# rs485.net
KiCad netlist of a schematic drawn in Altium Designer
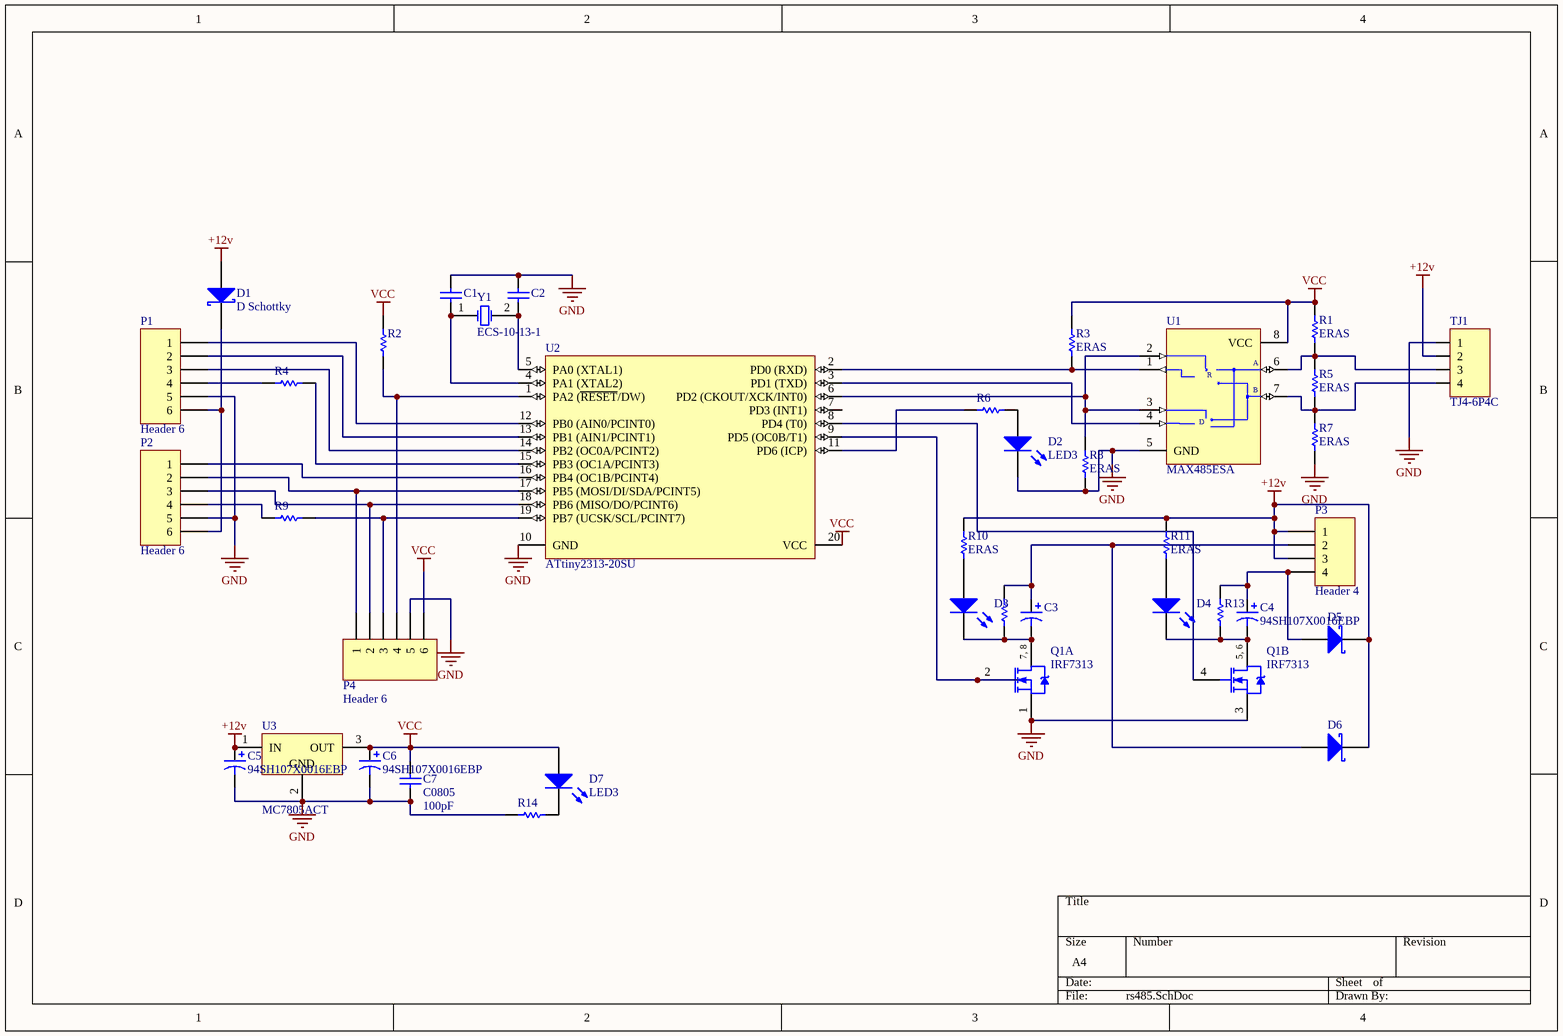
[diagram p0: rs485.SchDoc]

(export (version "E")
  (design (tool "Eeschema 10.0.6"))
  (components
    (comp (ref "C1")
      (value "C0805")
      (footprint "0805")
      (description "Ceramic Chip Capacitor - Standard")
      (fields (field (name "PUBLISHER") "Altium Limited"))
      (libsource (lib "KEMET Chip Capacitor") (part "C0805"))
    )
    (comp (ref "C2")
      (value "C0805")
      (footprint "0805")
      (description "Ceramic Chip Capacitor - Standard")
      (fields (field (name "PUBLISHER") "Altium Limited"))
      (libsource (lib "KEMET Chip Capacitor") (part "C0805"))
    )
    (comp (ref "C3")
      (value "94SH107X0016EBP")
      (footprint "E")
      (description "Solid Aluminum Capacitor with Organic Semiconductor Electrolyte: 100uF, 16V, Bulk Pack")
      (fields (field (name "PUBLISHER") "Altium Limited"))
      (libsource (lib "Vishay Electrolytic Radial-Lead Capacitor") (part "94SH107X0016EBP"))
    )
    (comp (ref "C4")
      (value "94SH107X0016EBP")
      (footprint "E")
      (description "Solid Aluminum Capacitor with Organic Semiconductor Electrolyte: 100uF, 16V, Bulk Pack")
      (fields (field (name "PUBLISHER") "Altium Limited"))
      (libsource (lib "Vishay Electrolytic Radial-Lead Capacitor") (part "94SH107X0016EBP"))
    )
    (comp (ref "C5")
      (value "94SH107X0016EBP")
      (footprint "E")
      (description "Solid Aluminum Capacitor with Organic Semiconductor Electrolyte: 100uF, 16V, Bulk Pack")
      (fields (field (name "PUBLISHER") "Altium Limited"))
      (libsource (lib "Vishay Electrolytic Radial-Lead Capacitor") (part "94SH107X0016EBP"))
    )
    (comp (ref "C6")
      (value "94SH107X0016EBP")
      (footprint "E")
      (description "Solid Aluminum Capacitor with Organic Semiconductor Electrolyte: 100uF, 16V, Bulk Pack")
      (fields (field (name "PUBLISHER") "Altium Limited"))
      (libsource (lib "Vishay Electrolytic Radial-Lead Capacitor") (part "94SH107X0016EBP"))
    )
    (comp (ref "C7")
      (value "C0805")
      (footprint "0805")
      (description "Ceramic Chip Capacitor - Standard")
      (fields (field (name "ALTIUM_VALUE") "100pF") (field (name "PUBLISHER") "Altium Limited"))
      (libsource (lib "KEMET Chip Capacitor") (part "C0805"))
    )
    (comp (ref "D1")
      (value "D Schottky")
      (footprint "SMB")
      (description "Schottky Diode")
      (fields (field (name "PUBLISHER") "Altium Limited"))
      (libsource (lib "Miscellaneous Devices") (part "D Schottky"))
    )
    (comp (ref "D2")
      (value "LED3")
      (footprint "3.5X2.8X1.9")
      (description "Typical BLUE SiC LED")
      (fields (field (name "PUBLISHER") "Altium Limited"))
      (libsource (lib "Miscellaneous Devices") (part "LED3"))
    )
    (comp (ref "D3")
      (value "LED3")
      (footprint "3.5X2.8X1.9")
      (description "Typical BLUE SiC LED")
      (fields (field (name "PUBLISHER") "Altium Limited"))
      (libsource (lib "Miscellaneous Devices") (part "LED3"))
    )
    (comp (ref "D4")
      (value "LED3")
      (footprint "3.5X2.8X1.9")
      (description "Typical BLUE SiC LED")
      (fields (field (name "PUBLISHER") "Altium Limited"))
      (libsource (lib "Miscellaneous Devices") (part "LED3"))
    )
    (comp (ref "D5")
      (value "D Schottky")
      (footprint "SMB")
      (description "Schottky Diode")
      (fields (field (name "PUBLISHER") "Altium Limited"))
      (libsource (lib "Miscellaneous Devices") (part "D Schottky"))
    )
    (comp (ref "D6")
      (value "D Schottky")
      (footprint "SMB")
      (description "Schottky Diode")
      (fields (field (name "PUBLISHER") "Altium Limited"))
      (libsource (lib "Miscellaneous Devices") (part "D Schottky"))
    )
    (comp (ref "D7")
      (value "LED3")
      (footprint "3.5X2.8X1.9")
      (description "Typical BLUE SiC LED")
      (fields (field (name "PUBLISHER") "Altium Limited"))
      (libsource (lib "Miscellaneous Devices") (part "LED3"))
    )
    (comp (ref "P1")
      (value "Header 6")
      (footprint "HDR1X6")
      (description "Header, 6-Pin")
      (fields (field (name "PUBLISHER") "Altium Limited"))
      (libsource (lib "") (part "Header 6_1"))
    )
    (comp (ref "P2")
      (value "Header 6")
      (footprint "HDR1X6")
      (description "Header, 6-Pin")
      (fields (field (name "PUBLISHER") "Altium Limited"))
      (libsource (lib "") (part "Header 6_1"))
    )
    (comp (ref "P3")
      (value "Header 4")
      (footprint "HDR1X4")
      (description "Header, 4-Pin")
      (fields (field (name "PUBLISHER") "Altium Limited"))
      (libsource (lib "Miscellaneous Connectors") (part "Header 4"))
    )
    (comp (ref "P4")
      (value "Header 6")
      (footprint "HDR1X6")
      (description "Header, 6-Pin")
      (fields (field (name "PUBLISHER") "Altium Limited"))
      (libsource (lib "Miscellaneous Connectors") (part "Header 6"))
    )
    (comp (ref "Q1")
      (value "IRF7313")
      (footprint "SO-8_N")
      (description "HEXFET Power MOSFET")
      (fields (field (name "PUBLISHER") "Altium Limited"))
      (libsource (lib "IR Discrete MOSFET - Power") (part "IRF7313"))
    )
    (comp (ref "R1")
      (value "ERAS")
      (footprint "ERA-0805")
      (fields (field (name "PUBLISHER") "Altium Limited"))
      (libsource (lib "Panasonic Resistor") (part "ERAS"))
    )
    (comp (ref "R2")
      (value "ERAS")
      (footprint "ERA-0805")
      (fields (field (name "PUBLISHER") "Altium Limited"))
      (libsource (lib "Panasonic Resistor") (part "ERAS"))
    )
    (comp (ref "R3")
      (value "ERAS")
      (footprint "ERA-0805")
      (fields (field (name "PUBLISHER") "Altium Limited"))
      (libsource (lib "Panasonic Resistor") (part "ERAS"))
    )
    (comp (ref "R4")
      (value "ERAS")
      (footprint "ERA-0805")
      (fields (field (name "PUBLISHER") "Altium Limited"))
      (libsource (lib "Panasonic Resistor") (part "ERAS"))
    )
    (comp (ref "R5")
      (value "ERAS")
      (footprint "ERA-0805")
      (fields (field (name "PUBLISHER") "Altium Limited"))
      (libsource (lib "Panasonic Resistor") (part "ERAS"))
    )
    (comp (ref "R6")
      (value "ERAS")
      (footprint "ERA-0805")
      (fields (field (name "PUBLISHER") "Altium Limited"))
      (libsource (lib "Panasonic Resistor") (part "ERAS"))
    )
    (comp (ref "R7")
      (value "ERAS")
      (footprint "ERA-0805")
      (fields (field (name "PUBLISHER") "Altium Limited"))
      (libsource (lib "Panasonic Resistor") (part "ERAS"))
    )
    (comp (ref "R8")
      (value "ERAS")
      (footprint "ERA-0805")
      (fields (field (name "PUBLISHER") "Altium Limited"))
      (libsource (lib "Panasonic Resistor") (part "ERAS"))
    )
    (comp (ref "R9")
      (value "ERAS")
      (footprint "ERA-0805")
      (fields (field (name "PUBLISHER") "Altium Limited"))
      (libsource (lib "Panasonic Resistor") (part "ERAS"))
    )
    (comp (ref "R10")
      (value "ERAS")
      (footprint "ERA-0805")
      (fields (field (name "PUBLISHER") "Altium Limited"))
      (libsource (lib "Panasonic Resistor") (part "ERAS"))
    )
    (comp (ref "R11")
      (value "ERAS")
      (footprint "ERA-0805")
      (fields (field (name "PUBLISHER") "Altium Limited"))
      (libsource (lib "Panasonic Resistor") (part "ERAS"))
    )
    (comp (ref "R12")
      (value "ERAS")
      (footprint "ERA-0805")
      (fields (field (name "PUBLISHER") "Altium Limited"))
      (libsource (lib "Panasonic Resistor") (part "ERAS"))
    )
    (comp (ref "R13")
      (value "ERAS")
      (footprint "ERA-0805")
      (fields (field (name "PUBLISHER") "Altium Limited"))
      (libsource (lib "Panasonic Resistor") (part "ERAS"))
    )
    (comp (ref "R14")
      (value "ERAS")
      (footprint "ERA-0805")
      (fields (field (name "PUBLISHER") "Altium Limited"))
      (libsource (lib "Panasonic Resistor") (part "ERAS"))
    )
    (comp (ref "TJ1") (value "TJ4-6P4C") (footprint "TJ4-6P4C") (libsource (lib "FAS") (part "TJ4-6P4C")))
    (comp (ref "U1")
      (value "MAX485ESA")
      (footprint "NSO8_N")
      (description "Low-Power, Slew-Rate-Limited RS-485/RS-422 Transceiver")
      (fields (field (name "PUBLISHER") "Altium Limited"))
      (libsource (lib "Maxim Communication Transceiver") (part "MAX485ESA"))
    )
    (comp (ref "U2")
      (value "ATtiny2313-20SU")
      (footprint "20S_N")
      (fields (field (name "PUBLISHER") "Altium Limited"))
      (libsource (lib "Atmel Microcontroller 8-Bit tinyAVR") (part "ATtiny2313-20SU"))
    )
    (comp (ref "U3")
      (value "MC7805ACT")
      (footprint "221A-06")
      (description "Three-Terminal Positive Voltage Regulator")
      (fields (field (name "PUBLISHER") "Altium Limited"))
      (libsource (lib "ON Semi Power Mgt Voltage Regulator") (part "MC7805ACT"))
    )
    (comp (ref "Y1")
      (value "ECS-10-13-1")
      (footprint "HC-49U")
      (description "Crystal Oscillator")
      (fields (field (name "PUBLISHER") "Altium Limited"))
      (libsource (lib "ECS Crystal Oscillator") (part "ECS-10-13-1"))
    )
  )
  (nets
    (net (code "1") (name "+12v") (class "Default")
      (node (ref "C5") (pin "1") (pinfunction "1_1") (pintype "passive"))
      (node (ref "D1") (pin "1") (pinfunction "A_1") (pintype "passive"))
      (node (ref "D5") (pin "2") (pinfunction "K_2") (pintype "passive"))
      (node (ref "D6") (pin "2") (pinfunction "K_2") (pintype "passive"))
      (node (ref "P3") (pin "1") (pinfunction "1_1") (pintype "passive"))
      (node (ref "P3") (pin "3") (pinfunction "3_3") (pintype "passive"))
      (node (ref "R10") (pin "1") (pinfunction "1_1") (pintype "passive"))
      (node (ref "R11") (pin "1") (pinfunction "1_1") (pintype "passive"))
      (node (ref "TJ1") (pin "2") (pinfunction "2_2") (pintype "passive"))
      (node (ref "U3") (pin "1") (pinfunction "IN_1") (pintype "power_in"))
    )
    (net (code "2") (name "GND") (class "Default")
      (node (ref "C1") (pin "1") (pinfunction "1_1") (pintype "passive"))
      (node (ref "C2") (pin "1") (pinfunction "1_1") (pintype "passive"))
      (node (ref "C5") (pin "2") (pinfunction "2_2") (pintype "passive"))
      (node (ref "C6") (pin "2") (pinfunction "2_2") (pintype "passive"))
      (node (ref "C7") (pin "1") (pinfunction "1_1") (pintype "passive"))
      (node (ref "D2") (pin "2") (pinfunction "K_2") (pintype "passive"))
      (node (ref "P1") (pin "5") (pinfunction "5_5") (pintype "passive"))
      (node (ref "P2") (pin "5") (pinfunction "5_5") (pintype "passive"))
      (node (ref "P4") (pin "5") (pinfunction "5_5") (pintype "passive"))
      (node (ref "Q1") (pin "1") (pinfunction "S_1") (pintype "passive"))
      (node (ref "Q1") (pin "3") (pinfunction "S_3") (pintype "passive"))
      (node (ref "R14") (pin "2") (pinfunction "2_2") (pintype "passive"))
      (node (ref "R7") (pin "2") (pinfunction "2_2") (pintype "passive"))
      (node (ref "R8") (pin "2") (pinfunction "2_2") (pintype "passive"))
      (node (ref "TJ1") (pin "1") (pinfunction "1_1") (pintype "passive"))
      (node (ref "U1") (pin "5") (pinfunction "GND_5") (pintype "power_in"))
      (node (ref "U2") (pin "10") (pinfunction "GND_10") (pintype "power_in"))
      (node (ref "U3") (pin "2") (pinfunction "GND_2") (pintype "power_in"))
    )
    (net (code "3") (name "Net-(D1-K)") (class "Default")
      (node (ref "D1") (pin "2") (pinfunction "K_2") (pintype "passive"))
      (node (ref "P1") (pin "6") (pinfunction "6_6") (pintype "passive"))
      (node (ref "P2") (pin "6") (pinfunction "6_6") (pintype "passive"))
    )
    (net (code "4") (name "Net-(D2-A)") (class "Default")
      (node (ref "D2") (pin "1") (pinfunction "A_1") (pintype "passive"))
      (node (ref "R6") (pin "2") (pinfunction "2_2") (pintype "passive"))
    )
    (net (code "5") (name "Net-(D3-A)") (class "Default")
      (node (ref "D3") (pin "1") (pinfunction "A_1") (pintype "passive"))
      (node (ref "R10") (pin "2") (pinfunction "2_2") (pintype "passive"))
    )
    (net (code "6") (name "Net-(D3-K)") (class "Default")
      (node (ref "C3") (pin "2") (pinfunction "2_2") (pintype "passive"))
      (node (ref "D3") (pin "2") (pinfunction "K_2") (pintype "passive"))
      (node (ref "Q1") (pin "7") (pinfunction "D_7") (pintype "passive"))
      (node (ref "Q1") (pin "8") (pinfunction "D_8") (pintype "passive"))
      (node (ref "R12") (pin "2") (pinfunction "2_2") (pintype "passive"))
    )
    (net (code "7") (name "Net-(D4-A)") (class "Default")
      (node (ref "D4") (pin "1") (pinfunction "A_1") (pintype "passive"))
      (node (ref "R11") (pin "2") (pinfunction "2_2") (pintype "passive"))
    )
    (net (code "8") (name "Net-(D4-K)") (class "Default")
      (node (ref "C4") (pin "2") (pinfunction "2_2") (pintype "passive"))
      (node (ref "D4") (pin "2") (pinfunction "K_2") (pintype "passive"))
      (node (ref "Q1") (pin "5") (pinfunction "D_5") (pintype "passive"))
      (node (ref "Q1") (pin "6") (pinfunction "D_6") (pintype "passive"))
      (node (ref "R13") (pin "2") (pinfunction "2_2") (pintype "passive"))
    )
    (net (code "9") (name "Net-(D5-A)") (class "Default")
      (node (ref "C4") (pin "1") (pinfunction "1_1") (pintype "passive"))
      (node (ref "D5") (pin "1") (pinfunction "A_1") (pintype "passive"))
      (node (ref "P3") (pin "4") (pinfunction "4_4") (pintype "passive"))
      (node (ref "R13") (pin "1") (pinfunction "1_1") (pintype "passive"))
    )
    (net (code "10") (name "Net-(D6-A)") (class "Default")
      (node (ref "C3") (pin "1") (pinfunction "1_1") (pintype "passive"))
      (node (ref "D6") (pin "1") (pinfunction "A_1") (pintype "passive"))
      (node (ref "P3") (pin "2") (pinfunction "2_2") (pintype "passive"))
      (node (ref "R12") (pin "1") (pinfunction "1_1") (pintype "passive"))
    )
    (net (code "11") (name "Net-(D7-K)") (class "Default")
      (node (ref "D7") (pin "2") (pinfunction "K_2") (pintype "passive"))
      (node (ref "R14") (pin "1") (pinfunction "1_1") (pintype "passive"))
    )
    (net (code "12") (name "Net-(P1-Pad4)") (class "Default")
      (node (ref "P1") (pin "4") (pinfunction "4_4") (pintype "passive"))
      (node (ref "R4") (pin "2") (pinfunction "2_2") (pintype "passive"))
    )
    (net (code "13") (name "Net-(P2-Pad4)") (class "Default")
      (node (ref "P2") (pin "4") (pinfunction "4_4") (pintype "passive"))
      (node (ref "R9") (pin "2") (pinfunction "2_2") (pintype "passive"))
    )
    (net (code "14") (name "Net-(Q1A-G)") (class "Default")
      (node (ref "Q1") (pin "2") (pinfunction "G_2") (pintype "passive"))
      (node (ref "U2") (pin "9") (pinfunction "PD5_(OC0B/T1)_9") (pintype "bidirectional"))
    )
    (net (code "15") (name "Net-(Q1B-G)") (class "Default")
      (node (ref "Q1") (pin "4") (pinfunction "G_4") (pintype "passive"))
      (node (ref "U2") (pin "8") (pinfunction "PD4_(T0)_8") (pintype "bidirectional"))
    )
    (net (code "16") (name "Net-(U1-A)") (class "Default")
      (node (ref "R1") (pin "2") (pinfunction "2_2") (pintype "passive"))
      (node (ref "R5") (pin "1") (pinfunction "1_1") (pintype "passive"))
      (node (ref "TJ1") (pin "3") (pinfunction "3_3") (pintype "passive"))
      (node (ref "U1") (pin "6") (pinfunction "A_6") (pintype "bidirectional"))
    )
    (net (code "17") (name "Net-(U1-B)") (class "Default")
      (node (ref "R5") (pin "2") (pinfunction "2_2") (pintype "passive"))
      (node (ref "R7") (pin "1") (pinfunction "1_1") (pintype "passive"))
      (node (ref "TJ1") (pin "4") (pinfunction "4_4") (pintype "passive"))
      (node (ref "U1") (pin "7") (pinfunction "B_7") (pintype "bidirectional"))
    )
    (net (code "18") (name "Net-(U1-DE)") (class "Default")
      (node (ref "R8") (pin "1") (pinfunction "1_1") (pintype "passive"))
      (node (ref "U1") (pin "2") (pinfunction "~{RE}_2") (pintype "input"))
      (node (ref "U1") (pin "3") (pinfunction "DE_3") (pintype "input"))
      (node (ref "U2") (pin "6") (pinfunction "PD2_(CKOUT/XCK/INT0)_6") (pintype "bidirectional"))
    )
    (net (code "19") (name "Net-(U1-DI)") (class "Default")
      (node (ref "U1") (pin "4") (pinfunction "DI_4") (pintype "input"))
      (node (ref "U2") (pin "3") (pinfunction "PD1_(TXD)_3") (pintype "bidirectional"))
    )
    (net (code "20") (name "Net-(U1-RO)") (class "Default")
      (node (ref "R3") (pin "2") (pinfunction "2_2") (pintype "passive"))
      (node (ref "U1") (pin "1") (pinfunction "RO_1") (pintype "output"))
      (node (ref "U2") (pin "2") (pinfunction "PD0_(RXD)_2") (pintype "bidirectional"))
    )
    (net (code "21") (name "Net-(U2-PA0_(XTAL1))") (class "Default")
      (node (ref "C2") (pin "2") (pinfunction "2_2") (pintype "passive"))
      (node (ref "U2") (pin "5") (pinfunction "PA0_(XTAL1)_5") (pintype "bidirectional"))
      (node (ref "Y1") (pin "2") (pinfunction "OSC2_2") (pintype "passive"))
    )
    (net (code "22") (name "Net-(U2-PA1_(XTAL2))") (class "Default")
      (node (ref "C1") (pin "2") (pinfunction "2_2") (pintype "passive"))
      (node (ref "U2") (pin "4") (pinfunction "PA1_(XTAL2)_4") (pintype "bidirectional"))
      (node (ref "Y1") (pin "1") (pinfunction "OSC1_1") (pintype "passive"))
    )
    (net (code "23") (name "Net-(U2-PA2_(~{RESET}{slash}DW))") (class "Default")
      (node (ref "P4") (pin "4") (pinfunction "4_4") (pintype "passive"))
      (node (ref "R2") (pin "2") (pinfunction "2_2") (pintype "passive"))
      (node (ref "U2") (pin "1") (pinfunction "PA2_(~{RESET}/DW)_1") (pintype "bidirectional"))
    )
    (net (code "24") (name "Net-(U2-PB0_(AIN0{slash}PCINT0))") (class "Default")
      (node (ref "P1") (pin "1") (pinfunction "1_1") (pintype "passive"))
      (node (ref "U2") (pin "12") (pinfunction "PB0_(AIN0/PCINT0)_12") (pintype "bidirectional"))
    )
    (net (code "25") (name "Net-(U2-PB1_(AIN1{slash}PCINT1))") (class "Default")
      (node (ref "P1") (pin "2") (pinfunction "2_2") (pintype "passive"))
      (node (ref "U2") (pin "13") (pinfunction "PB1_(AIN1/PCINT1)_13") (pintype "bidirectional"))
    )
    (net (code "26") (name "Net-(U2-PB2_(OC0A{slash}PCINT2))") (class "Default")
      (node (ref "P1") (pin "3") (pinfunction "3_3") (pintype "passive"))
      (node (ref "U2") (pin "14") (pinfunction "PB2_(OC0A/PCINT2)_14") (pintype "bidirectional"))
    )
    (net (code "27") (name "Net-(U2-PB3_(OC1A{slash}PCINT3))") (class "Default")
      (node (ref "R4") (pin "1") (pinfunction "1_1") (pintype "passive"))
      (node (ref "U2") (pin "15") (pinfunction "PB3_(OC1A/PCINT3)_15") (pintype "bidirectional"))
    )
    (net (code "28") (name "Net-(U2-PB4_(OC1B{slash}PCINT4))") (class "Default")
      (node (ref "P2") (pin "1") (pinfunction "1_1") (pintype "passive"))
      (node (ref "U2") (pin "16") (pinfunction "PB4_(OC1B/PCINT4)_16") (pintype "bidirectional"))
    )
    (net (code "29") (name "Net-(U2-PB5_(MOSI{slash}DI{slash}SDA{slash}PCINT5))") (class "Default")
      (node (ref "P2") (pin "2") (pinfunction "2_2") (pintype "passive"))
      (node (ref "P4") (pin "1") (pinfunction "1_1") (pintype "passive"))
      (node (ref "U2") (pin "17") (pinfunction "PB5_(MOSI/DI/SDA/PCINT5)_17") (pintype "bidirectional"))
    )
    (net (code "30") (name "Net-(U2-PB6_(MISO{slash}DO{slash}PCINT6))") (class "Default")
      (node (ref "P2") (pin "3") (pinfunction "3_3") (pintype "passive"))
      (node (ref "P4") (pin "2") (pinfunction "2_2") (pintype "passive"))
      (node (ref "U2") (pin "18") (pinfunction "PB6_(MISO/DO/PCINT6)_18") (pintype "bidirectional"))
    )
    (net (code "31") (name "Net-(U2-PB7_(UCSK{slash}SCL{slash}PCINT7))") (class "Default")
      (node (ref "P4") (pin "3") (pinfunction "3_3") (pintype "passive"))
      (node (ref "R9") (pin "1") (pinfunction "1_1") (pintype "passive"))
      (node (ref "U2") (pin "19") (pinfunction "PB7_(UCSK/SCL/PCINT7)_19") (pintype "bidirectional"))
    )
    (net (code "32") (name "Net-(U2-PD6_(ICP))") (class "Default")
      (node (ref "R6") (pin "1") (pinfunction "1_1") (pintype "passive"))
      (node (ref "U2") (pin "11") (pinfunction "PD6_(ICP)_11") (pintype "bidirectional"))
    )
    (net (code "33") (name "VCC") (class "Default")
      (node (ref "C6") (pin "1") (pinfunction "1_1") (pintype "passive"))
      (node (ref "C7") (pin "2") (pinfunction "2_2") (pintype "passive"))
      (node (ref "D7") (pin "1") (pinfunction "A_1") (pintype "passive"))
      (node (ref "P4") (pin "6") (pinfunction "6_6") (pintype "passive"))
      (node (ref "R1") (pin "1") (pinfunction "1_1") (pintype "passive"))
      (node (ref "R2") (pin "1") (pinfunction "1_1") (pintype "passive"))
      (node (ref "R3") (pin "1") (pinfunction "1_1") (pintype "passive"))
      (node (ref "U1") (pin "8") (pinfunction "VCC_8") (pintype "power_in"))
      (node (ref "U2") (pin "20") (pinfunction "VCC_20") (pintype "power_in"))
      (node (ref "U3") (pin "3") (pinfunction "OUT_3") (pintype "power_in"))
    )
    (net (code "34") (name "unconnected-(U2-PD3_(INT1)-Pad7)") (class "Default")
      (node (ref "U2") (pin "7") (pinfunction "PD3_(INT1)_7") (pintype "bidirectional"))
    )
  )
)
